# Sound.net
KiCad netlist of a schematic drawn in Altium Designer
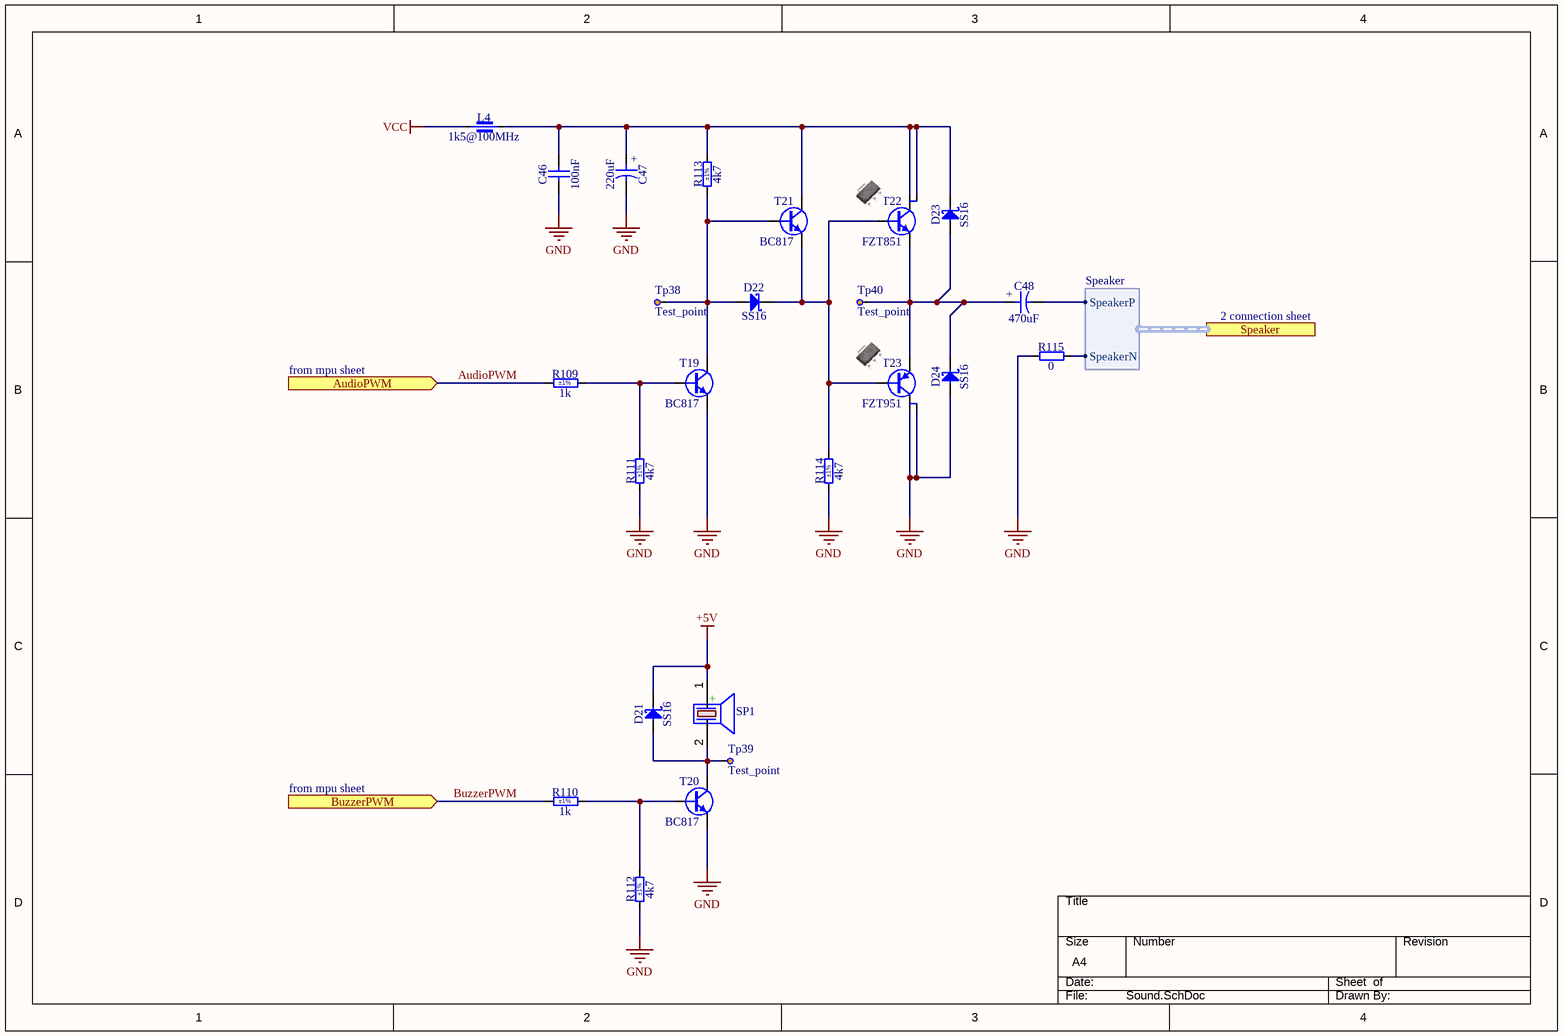
[diagram p0: Sound.SchDoc]

(export (version "E")
  (design (tool "Eeschema 10.0.6"))
  (components
    (comp (ref "C46")
      (value "100nF")
      (footprint "CAPC3216X140N")
      (description "Non-polarised capacitor")
      (fields
        (field (name "PART NUMBER") "CC1206_100NF_100V_10%_X7R")
        (field (name "VOLTAGE") "100V")
        (field (name "AUTHOR") "CERN DEM JLC")
      )
      (libsource (lib "Capacitors") (part "Capacitor - non polarized"))
    )
    (comp (ref "C47")
      (value "220uF")
      (footprint "CAPAE830X1020N")
      (description "Polarised capacitor")
      (fields
        (field (name "PART NUMBER") "CAE830-1020_220UF_50V_20%")
        (field (name "VOLTAGE") "50V")
        (field (name "AUTHOR") "CERN DEM BC")
      )
      (libsource (lib "Capacitors") (part "Capacitor - polarized"))
    )
    (comp (ref "C48")
      (value "470uF")
      (footprint "CAPPR500-1050X1750")
      (description "Polarised capacitor")
      (fields
        (field (name "PART NUMBER") "CAER_470UF_35V_20%_VISHAY_MAL203850471E3")
        (field (name "VOLTAGE") "35V")
        (field (name "AUTHOR") "CERN DEM JLC")
      )
      (libsource (lib "Capacitors") (part "Capacitor - polarized"))
    )
    (comp (ref "D21")
      (value "SS16")
      (footprint "DIOM5127X229N")
      (description "Schottky Diode")
      (fields
        (field (name "VOLTAGE") "60V")
        (field (name "POWER") "1A")
        (field (name "AUTHOR") "CERN DEM JLC")
      )
      (libsource (lib "ICs And Semiconductors") (part "Diode Schottky"))
    )
    (comp (ref "D22")
      (value "SS16")
      (footprint "DIOM5127X229N")
      (description "Schottky Diode")
      (fields
        (field (name "VOLTAGE") "60V")
        (field (name "POWER") "1A")
        (field (name "AUTHOR") "CERN DEM JLC")
      )
      (libsource (lib "ICs And Semiconductors") (part "Diode Schottky"))
    )
    (comp (ref "D23")
      (value "SS16")
      (footprint "DIOM5127X229N")
      (description "Schottky Diode")
      (fields
        (field (name "VOLTAGE") "60V")
        (field (name "POWER") "1A")
        (field (name "AUTHOR") "CERN DEM JLC")
      )
      (libsource (lib "ICs And Semiconductors") (part "Diode Schottky"))
    )
    (comp (ref "D24")
      (value "SS16")
      (footprint "DIOM5127X229N")
      (description "Schottky Diode")
      (fields
        (field (name "VOLTAGE") "60V")
        (field (name "POWER") "1A")
        (field (name "AUTHOR") "CERN DEM JLC")
      )
      (libsource (lib "ICs And Semiconductors") (part "Diode Schottky"))
    )
    (comp (ref "L4")
      (value "1k5@100MHz")
      (footprint "INDC2012X110N")
      (fields
        (field (name "PART NUMBER") "IND0805_WURTH_742792097")
        (field (name "POWER") "1A")
        (field (name "TOLERANCE") "±25%")
        (field (name "AUTHOR") "CERN DEM MR")
      )
      (libsource (lib "Inductors & Transformers") (part "Ferrite Bead"))
    )
    (comp (ref "R109")
      (value "1k")
      (footprint "RESC1608X55N")
      (description "Resistor - 1%")
      (fields
        (field (name "TOLERANCE") "±1%")
        (field (name "PART NUMBER") "R0603_1K_1%_0.1W_100PPM")
        (field (name "POWER") "0.1W")
        (field (name "AUTHOR") "CERN DEM JLC")
      )
      (libsource (lib "Resistors") (part "Resistor - 1%"))
    )
    (comp (ref "R110")
      (value "1k")
      (footprint "RESC1608X55N")
      (description "Resistor - 1%")
      (fields
        (field (name "TOLERANCE") "±1%")
        (field (name "PART NUMBER") "R0603_1K_1%_0.1W_100PPM")
        (field (name "POWER") "0.1W")
        (field (name "AUTHOR") "CERN DEM JLC")
      )
      (libsource (lib "Resistors") (part "Resistor - 1%"))
    )
    (comp (ref "R111")
      (value "4k7")
      (footprint "RESC1608X55N")
      (description "Resistor - 1%")
      (fields
        (field (name "TOLERANCE") "±1%")
        (field (name "PART NUMBER") "R0603_4K7_1%_0.1W_100PPM")
        (field (name "POWER") "0.1W")
        (field (name "AUTHOR") "CERN DEM JLC")
      )
      (libsource (lib "Resistors") (part "Resistor - 1%"))
    )
    (comp (ref "R112")
      (value "4k7")
      (footprint "RESC1608X55N")
      (description "Resistor - 1%")
      (fields
        (field (name "TOLERANCE") "±1%")
        (field (name "PART NUMBER") "R0603_4K7_1%_0.1W_100PPM")
        (field (name "POWER") "0.1W")
        (field (name "AUTHOR") "CERN DEM JLC")
      )
      (libsource (lib "Resistors") (part "Resistor - 1%"))
    )
    (comp (ref "R113")
      (value "4k7")
      (footprint "RESC3216X65N")
      (description "Resistor - 1%")
      (fields
        (field (name "TOLERANCE") "±1%")
        (field (name "PART NUMBER") "R1206_4K7_1%_0.25W_100PPM")
        (field (name "POWER") "0.25W")
        (field (name "AUTHOR") "CERN DEM JLC")
      )
      (libsource (lib "Resistors") (part "Resistor - 1%"))
    )
    (comp (ref "R114")
      (value "4k7")
      (footprint "RESC3216X65N")
      (description "Resistor - 1%")
      (fields
        (field (name "TOLERANCE") "±1%")
        (field (name "PART NUMBER") "R1206_4K7_1%_0.25W_100PPM")
        (field (name "POWER") "0.25W")
        (field (name "AUTHOR") "CERN DEM JLC")
      )
      (libsource (lib "Resistors") (part "Resistor - 1%"))
    )
    (comp (ref "R115")
      (value "0")
      (footprint "RESC1608X55N")
      (description "Resistor")
      (fields
        (field (name "PART NUMBER") "R0603_0R_JUMPER")
        (field (name "MANUFACTURER") "GENERIC")
        (field (name "AUTHOR") "CERN DEM JLC")
      )
      (libsource (lib "Resistors") (part "Resistor"))
    )
    (comp (ref "SP1")
      (value "~")
      (footprint "BUZZER 7.62mm DC")
      (description "PIEZO BUZZER ACTIVE")
      (fields (field (name "DESIGNER") "Abbas Basereh") (field (name "PUBLISHER") "Abbas Basereh"))
      (libsource (lib "2017AbbasBasereh9365731239 -ver1") (part "PIEZO BUZZER"))
    )
    (comp (ref "T19")
      (value "BC817")
      (footprint "SOT95P230X110-3N")
      (description "NPN Transistor")
      (fields (field (name "MANUFACTURER") "NXP SEMICONDUCTORS") (field (name "AUTHOR") "CERN DEM JLC"))
      (libsource (lib "ICs And Semiconductors") (part "NPN B1 E2 C3"))
    )
    (comp (ref "T20")
      (value "BC817")
      (footprint "SOT95P230X110-3N")
      (description "NPN Transistor")
      (fields (field (name "MANUFACTURER") "NXP SEMICONDUCTORS") (field (name "AUTHOR") "CERN DEM JLC"))
      (libsource (lib "ICs And Semiconductors") (part "NPN B1 E2 C3"))
    )
    (comp (ref "T21")
      (value "BC817")
      (footprint "SOT95P230X110-3N")
      (description "NPN Transistor")
      (fields (field (name "MANUFACTURER") "NXP SEMICONDUCTORS") (field (name "AUTHOR") "CERN DEM JLC"))
      (libsource (lib "ICs And Semiconductors") (part "NPN B1 E2 C3"))
    )
    (comp (ref "T22")
      (value "FZT851")
      (footprint "SOT230P700X180-4N")
      (description "NPN Transistor")
      (fields (field (name "MANUFACTURER") "ZETEX SEMICONDUCTORS") (field (name "AUTHOR") "CERN DEM JLC"))
      (libsource (lib "ICs And Semiconductors") (part "NPN B1 C2 E3 C4"))
    )
    (comp (ref "T23")
      (value "FZT951")
      (footprint "SOT230P700X180-4N")
      (description "PNP Transistor")
      (fields (field (name "MANUFACTURER") "ZETEX SEMICONDUCTORS") (field (name "AUTHOR") "CERN DEM JLC"))
      (libsource (lib "ICs And Semiconductors") (part "PNP B1 C2 E3 C4"))
    )
    (comp (ref "Tp38")
      (value "Test_point")
      (footprint "fromST:TP_C40")
      (description "Test point")
      (fields (field (name "PUBLISHER") "Altium Limited"))
      (libsource (lib "Sajad_Altium_Library") (part "Test point"))
    )
    (comp (ref "Tp39")
      (value "Test_point")
      (footprint "fromST:TP_C40")
      (description "Test point")
      (fields (field (name "PUBLISHER") "Altium Limited"))
      (libsource (lib "Sajad_Altium_Library") (part "Test point"))
    )
    (comp (ref "Tp40")
      (value "Test_point")
      (footprint "fromST:TP_C40")
      (description "Test point")
      (fields (field (name "PUBLISHER") "Altium Limited"))
      (libsource (lib "Sajad_Altium_Library") (part "Test point"))
    )
  )
  (nets
    (net (code "2") (name "+5V") (class "Default")
      (node (ref "D21") (pin "1") (pinfunction "C_1") (pintype "passive"))
      (node (ref "SP1") (pin "1") (pinfunction "+_1") (pintype "passive"))
    )
    (net (code "3") (name "/AudioPWM") (class "Default")
      (node (ref "R109") (pin "1") (pinfunction "1_1") (pintype "passive"))
    )
    (net (code "4") (name "/BuzzerPWM") (class "Default")
      (node (ref "R110") (pin "1") (pinfunction "1_1") (pintype "passive"))
    )
    (net (code "5") (name "/SpeakerN") (class "Default")
      (node (ref "R115") (pin "2") (pinfunction "2_2") (pintype "passive"))
    )
    (net (code "6") (name "/SpeakerP") (class "Default")
      (node (ref "C48") (pin "2") (pinfunction "2_2") (pintype "passive"))
    )
    (net (code "8") (name "GND") (class "Default")
      (node (ref "C46") (pin "1") (pinfunction "1_1") (pintype "passive"))
      (node (ref "C47") (pin "2") (pinfunction "2_2") (pintype "passive"))
      (node (ref "D24") (pin "2") (pinfunction "A_2") (pintype "passive"))
      (node (ref "R111") (pin "1") (pinfunction "1_1") (pintype "passive"))
      (node (ref "R112") (pin "1") (pinfunction "1_1") (pintype "passive"))
      (node (ref "R114") (pin "1") (pinfunction "1_1") (pintype "passive"))
      (node (ref "R115") (pin "1") (pinfunction "1_1") (pintype "passive"))
      (node (ref "T19") (pin "2") (pinfunction "E_2") (pintype "passive"))
      (node (ref "T20") (pin "2") (pinfunction "E_2") (pintype "passive"))
      (node (ref "T23") (pin "2") (pinfunction "C_2") (pintype "passive"))
      (node (ref "T23") (pin "4") (pinfunction "C_4") (pintype "passive"))
    )
    (net (code "9") (name "Net-(D21-A)") (class "Default")
      (node (ref "D21") (pin "2") (pinfunction "A_2") (pintype "passive"))
      (node (ref "SP1") (pin "2") (pinfunction "-_2") (pintype "passive"))
      (node (ref "T20") (pin "3") (pinfunction "C_3") (pintype "passive"))
      (node (ref "Tp39") (pin "1") (pinfunction "1_1") (pintype "passive"))
    )
    (net (code "10") (name "Net-(D22-A)") (class "Default")
      (node (ref "D22") (pin "2") (pinfunction "A_2") (pintype "passive"))
      (node (ref "R113") (pin "1") (pinfunction "1_1") (pintype "passive"))
      (node (ref "T19") (pin "3") (pinfunction "C_3") (pintype "passive"))
      (node (ref "T21") (pin "1") (pinfunction "B_1") (pintype "passive"))
      (node (ref "Tp38") (pin "1") (pinfunction "1_1") (pintype "passive"))
    )
    (net (code "11") (name "Net-(D22-C)") (class "Default")
      (node (ref "D22") (pin "1") (pinfunction "C_1") (pintype "passive"))
      (node (ref "R114") (pin "2") (pinfunction "2_2") (pintype "passive"))
      (node (ref "T21") (pin "2") (pinfunction "E_2") (pintype "passive"))
      (node (ref "T22") (pin "1") (pinfunction "B_1") (pintype "passive"))
      (node (ref "T23") (pin "1") (pinfunction "B_1") (pintype "passive"))
    )
    (net (code "12") (name "Net-(D23-A)") (class "Default")
      (node (ref "C48") (pin "1") (pinfunction "1_1") (pintype "passive"))
      (node (ref "D23") (pin "2") (pinfunction "A_2") (pintype "passive"))
      (node (ref "D24") (pin "1") (pinfunction "C_1") (pintype "passive"))
      (node (ref "T22") (pin "3") (pinfunction "E_3") (pintype "passive"))
      (node (ref "T23") (pin "3") (pinfunction "E_3") (pintype "passive"))
      (node (ref "Tp40") (pin "1") (pinfunction "1_1") (pintype "passive"))
    )
    (net (code "13") (name "Net-(D23-C)") (class "Default")
      (node (ref "C46") (pin "2") (pinfunction "2_2") (pintype "passive"))
      (node (ref "C47") (pin "1") (pinfunction "1_1") (pintype "passive"))
      (node (ref "D23") (pin "1") (pinfunction "C_1") (pintype "passive"))
      (node (ref "L4") (pin "2") (pinfunction "2_2") (pintype "passive"))
      (node (ref "R113") (pin "2") (pinfunction "2_2") (pintype "passive"))
      (node (ref "T21") (pin "3") (pinfunction "C_3") (pintype "passive"))
      (node (ref "T22") (pin "2") (pinfunction "C_2") (pintype "passive"))
      (node (ref "T22") (pin "4") (pinfunction "C_4") (pintype "passive"))
    )
    (net (code "14") (name "Net-(T19-B)") (class "Default")
      (node (ref "R109") (pin "2") (pinfunction "2_2") (pintype "passive"))
      (node (ref "R111") (pin "2") (pinfunction "2_2") (pintype "passive"))
      (node (ref "T19") (pin "1") (pinfunction "B_1") (pintype "passive"))
    )
    (net (code "15") (name "Net-(T20-B)") (class "Default")
      (node (ref "R110") (pin "2") (pinfunction "2_2") (pintype "passive"))
      (node (ref "R112") (pin "2") (pinfunction "2_2") (pintype "passive"))
      (node (ref "T20") (pin "1") (pinfunction "B_1") (pintype "passive"))
    )
    (net (code "16") (name "VCC") (class "Default")
      (node (ref "L4") (pin "1") (pinfunction "1_1") (pintype "passive"))
    )
  )
)
